# LSM6DSV_MAG_JST125.net
KiCad netlist of a schematic drawn in EasyEDA Pro
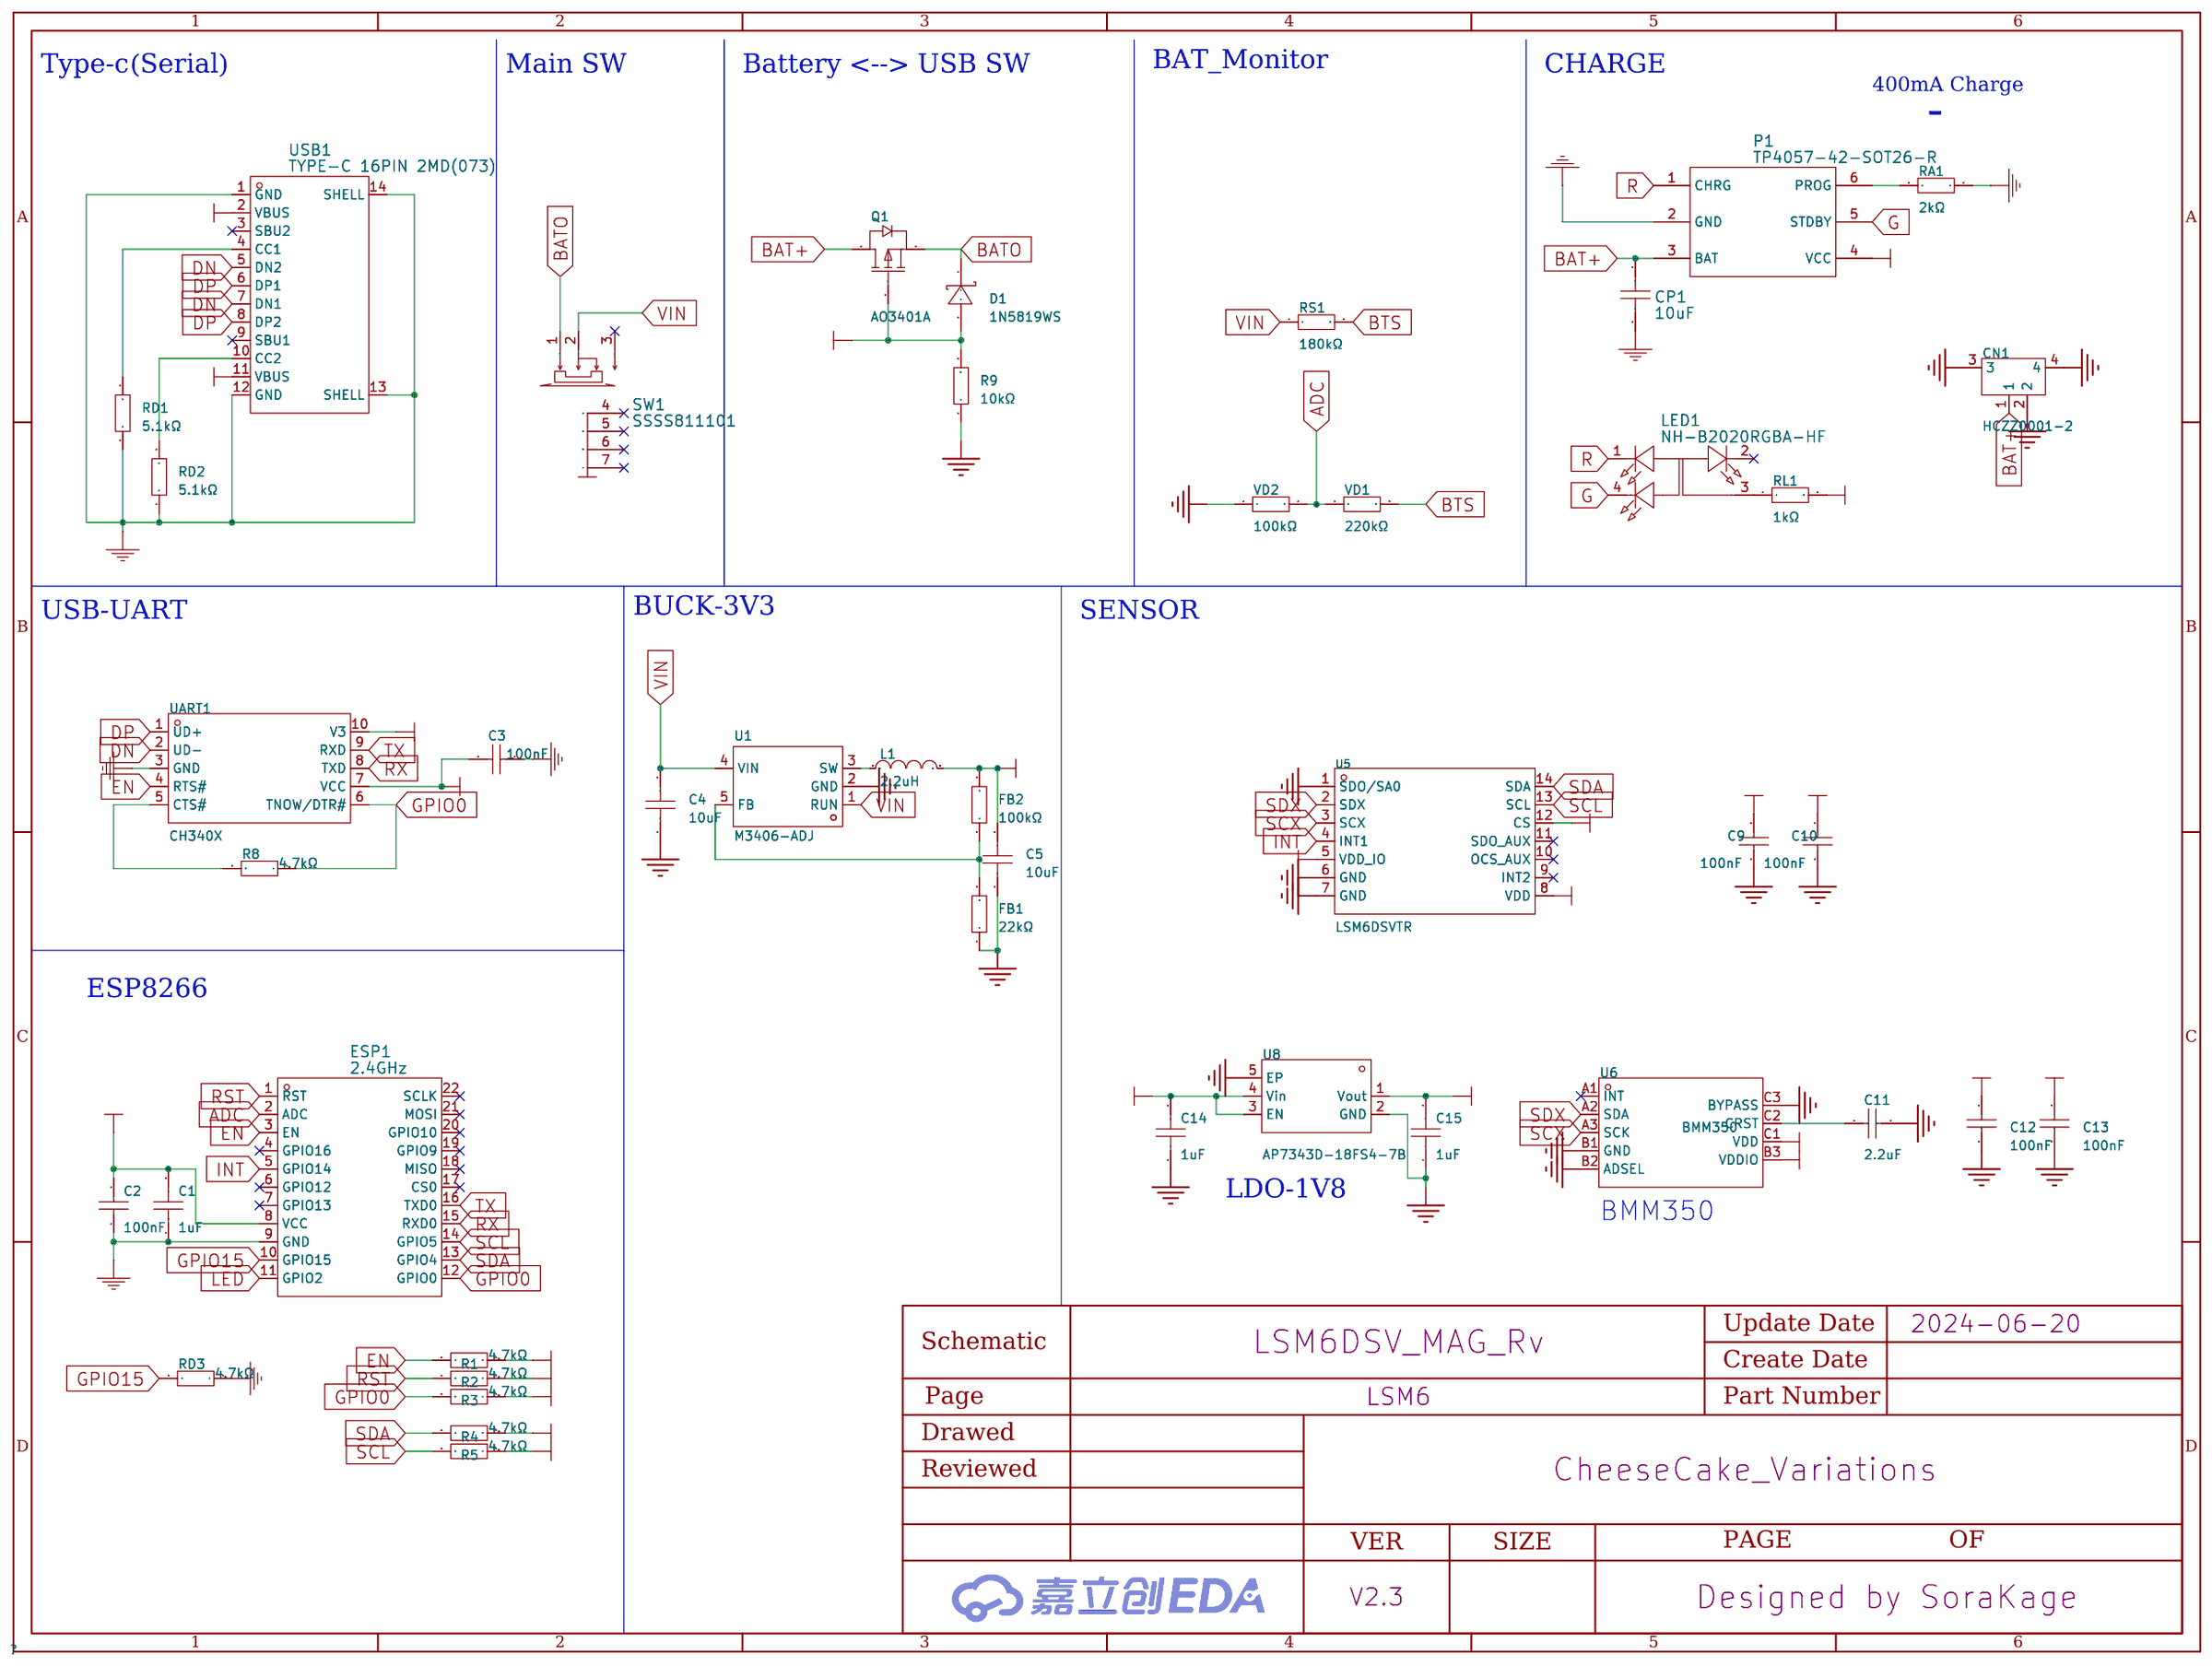
[diagram p0: schematic sheet]

(export (version "E")
  (design (tool "Eeschema 10.0.6"))
  (components
    (comp (ref "C1")
      (value "1uF")
      (footprint "easyedapro:C0402")
      (description "容值:1uF;精度:±10%;额定电压:25V;材质(温度系数):X5R;")
      (fields
        (field (name "Manufacturer Part") "CL05A105KA5NQNC")
        (field (name "Manufacturer") "SAMSUNG(三星)")
      )
      (libsource (lib "easyedapro") (part "CL05A105KA5NQNC"))
    )
    (comp (ref "C2")
      (value "100nF")
      (footprint "easyedapro:C0402")
      (description "容值:100nF;精度:±10%;额定电压:16V;材质(温度系数):X7R;")
      (fields
        (field (name "Manufacturer Part") "CL05B104KO5NNNC")
        (field (name "Manufacturer") "SAMSUNG(三星)")
      )
      (libsource (lib "easyedapro") (part "CL05B104KO5NNNC"))
    )
    (comp (ref "C3")
      (value "100nF")
      (footprint "easyedapro:C0402")
      (description "容值:100nF;精度:±10%;额定电压:16V;材质(温度系数):X7R;")
      (fields
        (field (name "Manufacturer Part") "CL05B104KO5NNNC")
        (field (name "Manufacturer") "SAMSUNG(三星)")
      )
      (libsource (lib "easyedapro") (part "CL05B104KO5NNNC"))
    )
    (comp (ref "C4")
      (value "10uF")
      (footprint "easyedapro:C0603")
      (description "容值:10uF;精度:±10%;额定电压:10V;材质(温度系数):X5R;")
      (fields
        (field (name "Manufacturer Part") "CL10A106KP8NNNC")
        (field (name "Manufacturer") "SAMSUNG(三星)")
      )
      (libsource (lib "easyedapro") (part "CL10A106KP8NNNC"))
    )
    (comp (ref "C5")
      (value "10uF")
      (footprint "easyedapro:C0603")
      (description "容值:10uF;精度:±10%;额定电压:10V;材质(温度系数):X5R;")
      (fields
        (field (name "Manufacturer Part") "CL10A106KP8NNNC")
        (field (name "Manufacturer") "SAMSUNG(三星)")
      )
      (libsource (lib "easyedapro") (part "CL10A106KP8NNNC"))
    )
    (comp (ref "C9")
      (value "100nF")
      (footprint "easyedapro:C0402")
      (description "容值:100nF;精度:±10%;额定电压:16V;材质(温度系数):X7R;")
      (fields
        (field (name "Manufacturer Part") "CL05B104KO5NNNC")
        (field (name "Manufacturer") "SAMSUNG(三星)")
      )
      (libsource (lib "easyedapro") (part "CL05B104KO5NNNC"))
    )
    (comp (ref "C10")
      (value "100nF")
      (footprint "easyedapro:C0402")
      (description "容值:100nF;精度:±10%;额定电压:16V;材质(温度系数):X7R;")
      (fields
        (field (name "Manufacturer Part") "CL05B104KO5NNNC")
        (field (name "Manufacturer") "SAMSUNG(三星)")
      )
      (libsource (lib "easyedapro") (part "CL05B104KO5NNNC"))
    )
    (comp (ref "C11")
      (value "2.2uF")
      (footprint "easyedapro:C0805")
      (description "容值:2.2uF;精度:±10%;额定电压:10V;材质(温度系数):X7R;")
      (fields
        (field (name "Manufacturer Part") "GCM21BR71A225KA37L")
        (field (name "Manufacturer") "muRata(村田)")
      )
      (libsource (lib "easyedapro") (part "GCM21BR71A225KA37L"))
    )
    (comp (ref "C12")
      (value "100nF")
      (footprint "easyedapro:C0402")
      (description "容值:100nF;精度:±10%;额定电压:16V;材质(温度系数):X7R;")
      (fields
        (field (name "Manufacturer Part") "CL05B104KO5NNNC")
        (field (name "Manufacturer") "SAMSUNG(三星)")
      )
      (libsource (lib "easyedapro") (part "CL05B104KO5NNNC"))
    )
    (comp (ref "C13")
      (value "100nF")
      (footprint "easyedapro:C0402")
      (description "容值:100nF;精度:±10%;额定电压:16V;材质(温度系数):X7R;")
      (fields
        (field (name "Manufacturer Part") "CL05B104KO5NNNC")
        (field (name "Manufacturer") "SAMSUNG(三星)")
      )
      (libsource (lib "easyedapro") (part "CL05B104KO5NNNC"))
    )
    (comp (ref "C14")
      (value "1uF")
      (footprint "easyedapro:C0402")
      (description "容值:1uF;精度:±10%;额定电压:25V;材质(温度系数):X5R;")
      (fields
        (field (name "Manufacturer Part") "CL05A105KA5NQNC")
        (field (name "Manufacturer") "SAMSUNG(三星)")
      )
      (libsource (lib "easyedapro") (part "CL05A105KA5NQNC"))
    )
    (comp (ref "C15")
      (value "1uF")
      (footprint "easyedapro:C0402")
      (description "容值:1uF;精度:±10%;额定电压:25V;材质(温度系数):X5R;")
      (fields
        (field (name "Manufacturer Part") "CL05A105KA5NQNC")
        (field (name "Manufacturer") "SAMSUNG(三星)")
      )
      (libsource (lib "easyedapro") (part "CL05A105KA5NQNC"))
    )
    (comp (ref "CN1")
      (value "HCZZ0001-2")
      (footprint "easyedapro:CONN-SMD_2P-P1.25_HC_HCZZ0001-2")
      (fields (field (name "Manufacturer") "HC(虹成电子)"))
      (libsource (lib "easyedapro") (part "HCZZ0001-2"))
    )
    (comp (ref "CP1")
      (value "10uF")
      (footprint "easyedapro:C0603")
      (fields
        (field (name "Manufacturer Part") "CL10A106KP8NNNC")
        (field (name "Manufacturer") "SAMSUNG(三星)")
      )
      (libsource (lib "easyedapro") (part "10uF"))
    )
    (comp (ref "D1")
      (value "1N5819WS")
      (footprint "easyedapro:SOD-323_L1.8-W1.3-LS2.5-RD")
      (description "直流反向耐压(Vr):40V;平均整流电流(Io):1A;正向压降(Vf):600mV@1A;")
      (fields (field (name "Manufacturer") "Hottech(合科泰)"))
      (libsource (lib "easyedapro") (part "1N5819WS"))
    )
    (comp (ref "ESP1")
      (value "2.4GHz")
      (description "核心处理器:ESP8266芯片;频率:2.4GHz;天线形式:板载PCB天线;发射功率:16dBm;接收灵敏度:-90dBm;")
      (fields
        (field (name "Manufacturer Part") "ESP-12F(ESP8266MOD)")
        (field (name "Manufacturer") "Ai-Thinker(安信可)")
      )
      (libsource (lib "easyedapro") (part "ESP-12F(ESP8266MOD)"))
    )
    (comp (ref "FB1")
      (value "22kΩ")
      (footprint "easyedapro:R0402")
      (description "电阻类型:厚膜电阻;阻值:22kΩ;精度:±1%;功率:62.5mW;")
      (fields
        (field (name "Manufacturer Part") "0402WGF2202TCE")
        (field (name "Manufacturer") "UNI-ROYAL(厚声)")
      )
      (libsource (lib "easyedapro") (part "0402WGF2202TCE"))
    )
    (comp (ref "FB2")
      (value "100kΩ")
      (footprint "easyedapro:R0402")
      (description "电阻类型:厚膜电阻;阻值:100kΩ;精度:±1%;功率:62.5mW;")
      (fields
        (field (name "Manufacturer Part") "0402WGF1003TCE")
        (field (name "Manufacturer") "UNI-ROYAL(厚声)")
      )
      (libsource (lib "easyedapro") (part "0402WGF1003TCE"))
    )
    (comp (ref "L1")
      (value "2.2uH")
      (footprint "easyedapro:IND-SMD_L2.5-W2.0_YXMBL252010P")
      (description "类型:一体成型电感;电感值:2.2uH;精度:±20%;额定电流:2.1A;饱和电流(Isat):3A;")
      (fields (field (name "Manufacturer Part") "APH252010T2R2M") (field (name "Manufacturer") "APV(爱普微)"))
      (libsource (lib "easyedapro") (part "APH252010T2R2M"))
    )
    (comp (ref "LED1")
      (value "NH-B2020RGBA-HF")
      (footprint "easyedapro:LED-ARRAY-SMD_4P-L2.1-W2.1-TL_NH-B2020RGBA")
      (fields (field (name "Manufacturer") "国星光电"))
      (libsource (lib "easyedapro") (part "NH-B2020RGBA-HF"))
    )
    (comp (ref "P1")
      (value "TP4057-42-SOT26-R")
      (footprint "easyedapro:SOT-23-6_L2.9-W1.6-P0.95-LS2.8-BL")
      (fields (field (name "Manufacturer") "TOPPOWER(南京拓微)"))
      (libsource (lib "easyedapro") (part "TP4057"))
    )
    (comp (ref "Q1")
      (value "AO3401A")
      (footprint "easyedapro:SOT-23_L2.9-W1.3-P1.90-LS2.4-BR")
      (description "类型:P沟道;漏源电压(Vdss):30V;连续漏极电流(Id):4A;功率(Pd):1.4W;导通电阻(RDS(on)@Vgs,Id):44mΩ@10V,4.3A;")
      (fields (field (name "Manufacturer") "AOS"))
      (libsource (lib "easyedapro") (part "AO3401A"))
    )
    (comp (ref "R1")
      (value "4.7kΩ")
      (footprint "easyedapro:R0402")
      (description "电阻类型:厚膜电阻;阻值:4.7kΩ;精度:±1%;功率:62.5mW;")
      (fields
        (field (name "Manufacturer Part") "0402WGF4701TCE")
        (field (name "Manufacturer") "UNI-ROYAL(厚声)")
      )
      (libsource (lib "easyedapro") (part "0402WGF4701TCE"))
    )
    (comp (ref "R2")
      (value "4.7kΩ")
      (footprint "easyedapro:R0402")
      (description "电阻类型:厚膜电阻;阻值:4.7kΩ;精度:±1%;功率:62.5mW;")
      (fields
        (field (name "Manufacturer Part") "0402WGF4701TCE")
        (field (name "Manufacturer") "UNI-ROYAL(厚声)")
      )
      (libsource (lib "easyedapro") (part "0402WGF4701TCE"))
    )
    (comp (ref "R3")
      (value "4.7kΩ")
      (footprint "easyedapro:R0402")
      (description "电阻类型:厚膜电阻;阻值:4.7kΩ;精度:±1%;功率:62.5mW;")
      (fields
        (field (name "Manufacturer Part") "0402WGF4701TCE")
        (field (name "Manufacturer") "UNI-ROYAL(厚声)")
      )
      (libsource (lib "easyedapro") (part "0402WGF4701TCE"))
    )
    (comp (ref "R4")
      (value "4.7kΩ")
      (footprint "easyedapro:R0402")
      (description "电阻类型:厚膜电阻;阻值:4.7kΩ;精度:±1%;功率:62.5mW;")
      (fields
        (field (name "Manufacturer Part") "0402WGF4701TCE")
        (field (name "Manufacturer") "UNI-ROYAL(厚声)")
      )
      (libsource (lib "easyedapro") (part "0402WGF4701TCE"))
    )
    (comp (ref "R5")
      (value "4.7kΩ")
      (footprint "easyedapro:R0402")
      (description "电阻类型:厚膜电阻;阻值:4.7kΩ;精度:±1%;功率:62.5mW;")
      (fields
        (field (name "Manufacturer Part") "0402WGF4701TCE")
        (field (name "Manufacturer") "UNI-ROYAL(厚声)")
      )
      (libsource (lib "easyedapro") (part "0402WGF4701TCE"))
    )
    (comp (ref "R8")
      (value "4.7kΩ")
      (footprint "easyedapro:R0402")
      (description "电阻类型:厚膜电阻;阻值:4.7kΩ;精度:±1%;功率:62.5mW;")
      (fields
        (field (name "Manufacturer Part") "0402WGF4701TCE")
        (field (name "Manufacturer") "UNI-ROYAL(厚声)")
      )
      (libsource (lib "easyedapro") (part "0402WGF4701TCE"))
    )
    (comp (ref "R9")
      (value "10kΩ")
      (footprint "easyedapro:R0402")
      (description "电阻类型:厚膜电阻;阻值:10kΩ;精度:±1%;功率:62.5mW;")
      (fields
        (field (name "Manufacturer Part") "0402WGF1002TCE")
        (field (name "Manufacturer") "UNI-ROYAL(厚声)")
      )
      (libsource (lib "easyedapro") (part "0402WGF1002TCE"))
    )
    (comp (ref "RA1")
      (value "2kΩ")
      (footprint "easyedapro:R0402")
      (description "电阻类型:厚膜电阻;阻值:2kΩ;精度:±1%;功率:62.5mW;")
      (fields
        (field (name "Manufacturer Part") "0402WGF2001TCE")
        (field (name "Manufacturer") "UNI-ROYAL(厚声)")
      )
      (libsource (lib "easyedapro") (part "0402WGF2001TCE"))
    )
    (comp (ref "RD1")
      (value "5.1kΩ")
      (footprint "easyedapro:R0402")
      (description "电阻类型:厚膜电阻;阻值:5.1kΩ;精度:±1%;功率:62.5mW;")
      (fields
        (field (name "Manufacturer Part") "0402WGF5101TCE")
        (field (name "Manufacturer") "UNI-ROYAL(厚声)")
      )
      (libsource (lib "easyedapro") (part "0402WGF5101TCE"))
    )
    (comp (ref "RD2")
      (value "5.1kΩ")
      (footprint "easyedapro:R0402")
      (description "电阻类型:厚膜电阻;阻值:5.1kΩ;精度:±1%;功率:62.5mW;")
      (fields
        (field (name "Manufacturer Part") "0402WGF5101TCE")
        (field (name "Manufacturer") "UNI-ROYAL(厚声)")
      )
      (libsource (lib "easyedapro") (part "0402WGF5101TCE"))
    )
    (comp (ref "RD3")
      (value "4.7kΩ")
      (footprint "easyedapro:R0402")
      (description "电阻类型:厚膜电阻;阻值:4.7kΩ;精度:±1%;功率:62.5mW;")
      (fields
        (field (name "Manufacturer Part") "0402WGF4701TCE")
        (field (name "Manufacturer") "UNI-ROYAL(厚声)")
      )
      (libsource (lib "easyedapro") (part "0402WGF4701TCE"))
    )
    (comp (ref "RL1")
      (value "1kΩ")
      (footprint "easyedapro:R0402")
      (description "电阻类型:厚膜电阻;阻值:1kΩ;精度:±1%;功率:62.5mW;")
      (fields
        (field (name "Manufacturer Part") "0402WGF1001TCE")
        (field (name "Manufacturer") "UNI-ROYAL(厚声)")
      )
      (libsource (lib "easyedapro") (part "0402WGF1001TCE"))
    )
    (comp (ref "RS1")
      (value "180kΩ")
      (footprint "easyedapro:R0402")
      (description "阻值:180kΩ;精度:±1%;功率:62.5mW;温度系数:±100ppm/°C;电阻类型:厚膜电阻;")
      (fields
        (field (name "Manufacturer Part") "0402WGF1803TCE")
        (field (name "Manufacturer") "UNI-ROYAL(厚声)")
      )
      (libsource (lib "easyedapro") (part "0402WGF1803TCE"))
    )
    (comp (ref "SW1")
      (value "SSSS811101")
      (footprint "easyedapro:SW-SMD_SSSS811101")
      (fields (field (name "Manufacturer") "ALPSALPINE(阿尔卑斯阿尔派)"))
      (libsource (lib "easyedapro") (part "SSSS811101"))
    )
    (comp (ref "U1")
      (value "M3406-ADJ")
      (footprint "easyedapro:SOT-23-5_L3.0-W1.7-P0.95-LS2.8-BR")
      (description "功能类型:降压型;同步整流:-;输出通道数:-;拓扑结构:-;输入电压:-;输出电流(最大值):-;开关频率:-;")
      (fields (field (name "Manufacturer") "西安航天民芯"))
      (libsource (lib "easyedapro") (part "M3406"))
    )
    (comp (ref "U5")
      (value "LSM6DSVTR")
      (footprint "easyedapro:LGA-14_L3.0-W2.5-P0.50-TL")
      (description "传感器类型:加速度计陀螺仪;")
      (fields (field (name "Manufacturer") "ST(意法半导体)"))
      (libsource (lib "easyedapro") (part "LSM6DSVTR"))
    )
    (comp (ref "U6")
      (value "BMM350")
      (footprint "easyedapro:WLCSP-9_L1.3-W1.3-R3-C3-P0.40-TL")
      (libsource (lib "easyedapro") (part "BMM350"))
    )
    (comp (ref "U8")
      (value "AP7343D-18FS4-7B")
      (footprint "easyedapro:X2-DFN1010-4_L1.0-W1.0-P0.65-BL-EP")
      (description "输出类型:固定;最大输入电压:5.25V;输出电压:1.8V;最大输出电流:300mA;电源纹波抑制比(PSRR):75dB@(1kHz);输出极性:正极;")
      (fields (field (name "Manufacturer") "DIODES(美台)"))
      (libsource (lib "easyedapro") (part "AP7343D-18FS4-7B"))
    )
    (comp (ref "UART1")
      (value "CH340X")
      (footprint "easyedapro:MSOP-10_L3.0-W3.0-P0.50-LS5.0-BL")
      (fields (field (name "Manufacturer") "WCH(南京沁恒)"))
      (libsource (lib "easyedapro") (part "CH340X"))
    )
    (comp (ref "USB1")
      (value "TYPE-C 16PIN 2MD(073)")
      (footprint "easyedapro:USB-C-SMD_TYPE-C-6PIN-2MD-073")
      (fields (field (name "Manufacturer") "SHOU HAN(首韩)"))
      (libsource (lib "easyedapro") (part "TYPE-C 16PIN 2MD(073)"))
    )
    (comp (ref "VD1")
      (value "220kΩ")
      (footprint "easyedapro:R0402")
      (description "电阻类型:厚膜电阻;阻值:220kΩ;精度:±1%;功率:62.5mW;")
      (fields
        (field (name "Manufacturer Part") "0402WGF2203TCE")
        (field (name "Manufacturer") "UNI-ROYAL(厚声)")
      )
      (libsource (lib "easyedapro") (part "0402WGF2203TCE"))
    )
    (comp (ref "VD2")
      (value "100kΩ")
      (footprint "easyedapro:R0402")
      (description "电阻类型:厚膜电阻;阻值:100kΩ;精度:±1%;功率:62.5mW;")
      (fields
        (field (name "Manufacturer Part") "0402WGF1003TCE")
        (field (name "Manufacturer") "UNI-ROYAL(厚声)")
      )
      (libsource (lib "easyedapro") (part "0402WGF1003TCE"))
    )
  )
  (nets
    (net (code "1") (name "+5V") (class "Default")
      (node (ref "D1") (pin "2") (pinfunction "A_2") (pintype "unspecified"))
      (node (ref "P1") (pin "4") (pinfunction "VCC_4") (pintype "unspecified"))
      (node (ref "Q1") (pin "1") (pinfunction "G_1") (pintype "input"))
      (node (ref "R9") (pin "2") (pinfunction "2_2") (pintype "input"))
      (node (ref "RL1") (pin "2") (pinfunction "2_2") (pintype "input"))
      (node (ref "USB1") (pin "11") (pinfunction "VBUS_11") (pintype "input"))
      (node (ref "USB1") (pin "2") (pinfunction "VBUS_2") (pintype "input"))
    )
    (net (code "2") (name "1V8") (class "Default")
      (node (ref "C12") (pin "2") (pinfunction "2_2") (pintype "input"))
      (node (ref "C15") (pin "2") (pinfunction "2_2") (pintype "unspecified"))
      (node (ref "U6") (pin "C1") (pinfunction "VDD_C1") (pintype "unspecified"))
      (node (ref "U8") (pin "1") (pinfunction "Vout_1") (pintype "input"))
    )
    (net (code "3") (name "3V3") (class "Default")
      (node (ref "C1") (pin "2") (pinfunction "2_2") (pintype "unspecified"))
      (node (ref "C10") (pin "1") (pinfunction "1_1") (pintype "input"))
      (node (ref "C13") (pin "2") (pinfunction "2_2") (pintype "input"))
      (node (ref "C14") (pin "2") (pinfunction "2_2") (pintype "unspecified"))
      (node (ref "C2") (pin "2") (pinfunction "2_2") (pintype "input"))
      (node (ref "C3") (pin "2") (pinfunction "2_2") (pintype "input"))
      (node (ref "C5") (pin "2") (pinfunction "2_2") (pintype "unspecified"))
      (node (ref "C9") (pin "1") (pinfunction "1_1") (pintype "input"))
      (node (ref "ESP1") (pin "8") (pinfunction "VCC_8") (pintype "input"))
      (node (ref "FB2") (pin "2") (pinfunction "2_2") (pintype "input"))
      (node (ref "L1") (pin "2") (pinfunction "2_2") (pintype "unspecified"))
      (node (ref "R1") (pin "1") (pinfunction "1_1") (pintype "input"))
      (node (ref "R2") (pin "1") (pinfunction "1_1") (pintype "input"))
      (node (ref "R3") (pin "1") (pinfunction "1_1") (pintype "input"))
      (node (ref "R4") (pin "1") (pinfunction "1_1") (pintype "input"))
      (node (ref "R5") (pin "1") (pinfunction "1_1") (pintype "input"))
      (node (ref "U5") (pin "12") (pinfunction "CS_12") (pintype "input"))
      (node (ref "U5") (pin "5") (pinfunction "VDD_IO_5") (pintype "input"))
      (node (ref "U5") (pin "8") (pinfunction "VDD_8") (pintype "input"))
      (node (ref "U6") (pin "B3") (pinfunction "VDDIO_B3") (pintype "unspecified"))
      (node (ref "U8") (pin "3") (pinfunction "EN_3") (pintype "input"))
      (node (ref "U8") (pin "4") (pinfunction "Vin_4") (pintype "input"))
      (node (ref "UART1") (pin "10") (pinfunction "V3_10") (pintype "unspecified"))
      (node (ref "UART1") (pin "7") (pinfunction "VCC_7") (pintype "unspecified"))
    )
    (net (code "4") (name "ADC") (class "Default")
      (node (ref "ESP1") (pin "2") (pinfunction "ADC_2") (pintype "input"))
      (node (ref "VD1") (pin "1") (pinfunction "1_1") (pintype "input"))
      (node (ref "VD2") (pin "2") (pinfunction "2_2") (pintype "input"))
    )
    (net (code "5") (name "BAT+") (class "Default")
      (node (ref "CN1") (pin "1") (pinfunction "1_1") (pintype "unspecified"))
      (node (ref "CP1") (pin "2") (pinfunction "2_2") (pintype "input"))
      (node (ref "P1") (pin "3") (pinfunction "BAT_3") (pintype "unspecified"))
      (node (ref "Q1") (pin "3") (pinfunction "D_3") (pintype "input"))
    )
    (net (code "6") (name "BATO") (class "Default")
      (node (ref "D1") (pin "1") (pinfunction "K_1") (pintype "unspecified"))
      (node (ref "Q1") (pin "2") (pinfunction "S_2") (pintype "input"))
      (node (ref "SW1") (pin "1") (pinfunction "1_1") (pintype "input"))
    )
    (net (code "7") (name "BTS") (class "Default")
      (node (ref "RS1") (pin "2") (pinfunction "2_2") (pintype "input"))
      (node (ref "VD1") (pin "2") (pinfunction "2_2") (pintype "input"))
    )
    (net (code "8") (name "DN") (class "Default")
      (node (ref "UART1") (pin "2") (pinfunction "UD-_2") (pintype "unspecified"))
      (node (ref "USB1") (pin "5") (pinfunction "DN2_5") (pintype "input"))
      (node (ref "USB1") (pin "7") (pinfunction "DN1_7") (pintype "input"))
    )
    (net (code "9") (name "DP") (class "Default")
      (node (ref "UART1") (pin "1") (pinfunction "UD+_1") (pintype "unspecified"))
      (node (ref "USB1") (pin "6") (pinfunction "DP1_6") (pintype "input"))
      (node (ref "USB1") (pin "8") (pinfunction "DP2_8") (pintype "input"))
    )
    (net (code "10") (name "EN") (class "Default")
      (node (ref "ESP1") (pin "3") (pinfunction "EN_3") (pintype "input"))
      (node (ref "R1") (pin "2") (pinfunction "2_2") (pintype "input"))
      (node (ref "UART1") (pin "4") (pinfunction "RTS#_4") (pintype "unspecified"))
    )
    (net (code "11") (name "G") (class "Default")
      (node (ref "LED1") (pin "4") (pinfunction "-_4") (pintype "input"))
      (node (ref "P1") (pin "5") (pinfunction "STDBY_5") (pintype "unspecified"))
    )
    (net (code "12") (name "GND") (class "Default")
      (node (ref "C1") (pin "1") (pinfunction "1_1") (pintype "unspecified"))
      (node (ref "C10") (pin "2") (pinfunction "2_2") (pintype "input"))
      (node (ref "C11") (pin "2") (pinfunction "2_2") (pintype "input"))
      (node (ref "C12") (pin "1") (pinfunction "1_1") (pintype "input"))
      (node (ref "C13") (pin "1") (pinfunction "1_1") (pintype "input"))
      (node (ref "C14") (pin "1") (pinfunction "1_1") (pintype "unspecified"))
      (node (ref "C15") (pin "1") (pinfunction "1_1") (pintype "unspecified"))
      (node (ref "C2") (pin "1") (pinfunction "1_1") (pintype "input"))
      (node (ref "C3") (pin "1") (pinfunction "1_1") (pintype "input"))
      (node (ref "C4") (pin "1") (pinfunction "1_1") (pintype "unspecified"))
      (node (ref "C5") (pin "1") (pinfunction "1_1") (pintype "unspecified"))
      (node (ref "C9") (pin "2") (pinfunction "2_2") (pintype "input"))
      (node (ref "CN1") (pin "2") (pinfunction "2_2") (pintype "unspecified"))
      (node (ref "CN1") (pin "3") (pinfunction "3_3") (pintype "unspecified"))
      (node (ref "CN1") (pin "4") (pinfunction "4_4") (pintype "unspecified"))
      (node (ref "CP1") (pin "1") (pinfunction "1_1") (pintype "input"))
      (node (ref "ESP1") (pin "9") (pinfunction "GND_9") (pintype "input"))
      (node (ref "FB1") (pin "1") (pinfunction "1_1") (pintype "input"))
      (node (ref "P1") (pin "2") (pinfunction "GND_2") (pintype "unspecified"))
      (node (ref "R9") (pin "1") (pinfunction "1_1") (pintype "input"))
      (node (ref "RA1") (pin "2") (pinfunction "2_2") (pintype "input"))
      (node (ref "RD1") (pin "1") (pinfunction "1_1") (pintype "input"))
      (node (ref "RD2") (pin "1") (pinfunction "1_1") (pintype "input"))
      (node (ref "RD3") (pin "1") (pinfunction "1_1") (pintype "input"))
      (node (ref "U1") (pin "2") (pinfunction "GND_2") (pintype "input"))
      (node (ref "U5") (pin "1") (pinfunction "SDO/SA0_1") (pintype "input"))
      (node (ref "U5") (pin "6") (pinfunction "GND_6") (pintype "input"))
      (node (ref "U5") (pin "7") (pinfunction "GND_7") (pintype "input"))
      (node (ref "U6") (pin "B1") (pinfunction "GND_B1") (pintype "unspecified"))
      (node (ref "U6") (pin "B2") (pinfunction "ADSEL_B2") (pintype "unspecified"))
      (node (ref "U6") (pin "C3") (pinfunction "BYPASS_C3") (pintype "unspecified"))
      (node (ref "U8") (pin "2") (pinfunction "GND_2") (pintype "input"))
      (node (ref "U8") (pin "5") (pinfunction "EP_5") (pintype "input"))
      (node (ref "UART1") (pin "3") (pinfunction "GND_3") (pintype "unspecified"))
      (node (ref "USB1") (pin "1") (pinfunction "GND_1") (pintype "input"))
      (node (ref "USB1") (pin "12") (pinfunction "GND_12") (pintype "input"))
      (node (ref "USB1") (pin "13") (pinfunction "SHELL_13") (pintype "input"))
      (node (ref "USB1") (pin "14") (pinfunction "SHELL_14") (pintype "input"))
      (node (ref "VD2") (pin "1") (pinfunction "1_1") (pintype "input"))
    )
    (net (code "13") (name "GPIO0") (class "Default")
      (node (ref "ESP1") (pin "12") (pinfunction "GPIO0_12") (pintype "input"))
      (node (ref "R3") (pin "2") (pinfunction "2_2") (pintype "input"))
      (node (ref "R8") (pin "1") (pinfunction "1_1") (pintype "input"))
      (node (ref "UART1") (pin "6") (pinfunction "TNOW/DTR#_6") (pintype "unspecified"))
    )
    (net (code "14") (name "GPIO15") (class "Default")
      (node (ref "ESP1") (pin "10") (pinfunction "GPIO15_10") (pintype "input"))
      (node (ref "RD3") (pin "2") (pinfunction "2_2") (pintype "input"))
    )
    (net (code "15") (name "INT") (class "Default")
      (node (ref "ESP1") (pin "5") (pinfunction "GPIO14_5") (pintype "input"))
      (node (ref "U5") (pin "4") (pinfunction "INT1_4") (pintype "input"))
    )
    (net (code "16") (name "LED") (class "Default")
      (node (ref "ESP1") (pin "11") (pinfunction "GPIO2_11") (pintype "input"))
    )
    (net (code "17") (name "Net-(LED1-+)") (class "Default")
      (node (ref "LED1") (pin "3") (pinfunction "+_3") (pintype "input"))
      (node (ref "RL1") (pin "1") (pinfunction "1_1") (pintype "input"))
    )
    (net (code "18") (name "Net-(P1-PROG)") (class "Default")
      (node (ref "P1") (pin "6") (pinfunction "PROG_6") (pintype "unspecified"))
      (node (ref "RA1") (pin "1") (pinfunction "1_1") (pintype "input"))
    )
    (net (code "19") (name "Net-(U1-FB)") (class "Default")
      (node (ref "FB1") (pin "2") (pinfunction "2_2") (pintype "input"))
      (node (ref "FB2") (pin "1") (pinfunction "1_1") (pintype "input"))
      (node (ref "U1") (pin "5") (pinfunction "FB_5") (pintype "input"))
    )
    (net (code "20") (name "Net-(U1-SW)") (class "Default")
      (node (ref "L1") (pin "1") (pinfunction "1_1") (pintype "unspecified"))
      (node (ref "U1") (pin "3") (pinfunction "SW_3") (pintype "input"))
    )
    (net (code "21") (name "Net-(U6-CRST)") (class "Default")
      (node (ref "C11") (pin "1") (pinfunction "1_1") (pintype "input"))
      (node (ref "U6") (pin "C2") (pinfunction "CRST_C2") (pintype "unspecified"))
    )
    (net (code "22") (name "Net-(UART1-CTS#)") (class "Default")
      (node (ref "R8") (pin "2") (pinfunction "2_2") (pintype "input"))
      (node (ref "UART1") (pin "5") (pinfunction "CTS#_5") (pintype "unspecified"))
    )
    (net (code "23") (name "Net-(USB1-CC1)") (class "Default")
      (node (ref "RD1") (pin "2") (pinfunction "2_2") (pintype "input"))
      (node (ref "USB1") (pin "4") (pinfunction "CC1_4") (pintype "input"))
    )
    (net (code "24") (name "Net-(USB1-CC2)") (class "Default")
      (node (ref "RD2") (pin "2") (pinfunction "2_2") (pintype "input"))
      (node (ref "USB1") (pin "10") (pinfunction "CC2_10") (pintype "input"))
    )
    (net (code "25") (name "R") (class "Default")
      (node (ref "LED1") (pin "1") (pinfunction "-_1") (pintype "input"))
      (node (ref "P1") (pin "1") (pinfunction "CHRG_1") (pintype "unspecified"))
    )
    (net (code "26") (name "RST") (class "Default")
      (node (ref "ESP1") (pin "1") (pinfunction "RST_1") (pintype "input"))
      (node (ref "R2") (pin "2") (pinfunction "2_2") (pintype "input"))
    )
    (net (code "27") (name "RX") (class "Default")
      (node (ref "ESP1") (pin "15") (pinfunction "RXD0_15") (pintype "input"))
      (node (ref "UART1") (pin "8") (pinfunction "TXD_8") (pintype "unspecified"))
    )
    (net (code "28") (name "SCL") (class "Default")
      (node (ref "ESP1") (pin "14") (pinfunction "GPIO5_14") (pintype "input"))
      (node (ref "R5") (pin "2") (pinfunction "2_2") (pintype "input"))
      (node (ref "U5") (pin "13") (pinfunction "SCL_13") (pintype "input"))
    )
    (net (code "29") (name "SCX") (class "Default")
      (node (ref "U5") (pin "3") (pinfunction "SCX_3") (pintype "input"))
      (node (ref "U6") (pin "A3") (pinfunction "SCK_A3") (pintype "unspecified"))
    )
    (net (code "30") (name "SDA") (class "Default")
      (node (ref "ESP1") (pin "13") (pinfunction "GPIO4_13") (pintype "input"))
      (node (ref "R4") (pin "2") (pinfunction "2_2") (pintype "input"))
      (node (ref "U5") (pin "14") (pinfunction "SDA_14") (pintype "input"))
    )
    (net (code "31") (name "SDX") (class "Default")
      (node (ref "U5") (pin "2") (pinfunction "SDX_2") (pintype "input"))
      (node (ref "U6") (pin "A2") (pinfunction "SDA_A2") (pintype "unspecified"))
    )
    (net (code "32") (name "TX") (class "Default")
      (node (ref "ESP1") (pin "16") (pinfunction "TXD0_16") (pintype "input"))
      (node (ref "UART1") (pin "9") (pinfunction "RXD_9") (pintype "unspecified"))
    )
    (net (code "33") (name "VIN") (class "Default")
      (node (ref "C4") (pin "2") (pinfunction "2_2") (pintype "unspecified"))
      (node (ref "RS1") (pin "1") (pinfunction "1_1") (pintype "input"))
      (node (ref "SW1") (pin "2") (pinfunction "2_2") (pintype "input"))
      (node (ref "U1") (pin "1") (pinfunction "RUN_1") (pintype "input"))
      (node (ref "U1") (pin "4") (pinfunction "VIN_4") (pintype "input"))
    )
    (net (code "34") (name "unconnected-(ESP1-CS0-Pad17)") (class "Default")
      (node (ref "ESP1") (pin "17") (pinfunction "CS0_17") (pintype "input+no_connect"))
    )
    (net (code "35") (name "unconnected-(ESP1-GPIO9-Pad19)") (class "Default")
      (node (ref "ESP1") (pin "19") (pinfunction "GPIO9_19") (pintype "input+no_connect"))
    )
    (net (code "36") (name "unconnected-(ESP1-GPIO10-Pad20)") (class "Default")
      (node (ref "ESP1") (pin "20") (pinfunction "GPIO10_20") (pintype "input+no_connect"))
    )
    (net (code "37") (name "unconnected-(ESP1-GPIO12-Pad6)") (class "Default")
      (node (ref "ESP1") (pin "6") (pinfunction "GPIO12_6") (pintype "input+no_connect"))
    )
    (net (code "38") (name "unconnected-(ESP1-GPIO13-Pad7)") (class "Default")
      (node (ref "ESP1") (pin "7") (pinfunction "GPIO13_7") (pintype "input+no_connect"))
    )
    (net (code "39") (name "unconnected-(ESP1-GPIO16-Pad4)") (class "Default")
      (node (ref "ESP1") (pin "4") (pinfunction "GPIO16_4") (pintype "input+no_connect"))
    )
    (net (code "40") (name "unconnected-(ESP1-MISO-Pad18)") (class "Default")
      (node (ref "ESP1") (pin "18") (pinfunction "MISO_18") (pintype "input+no_connect"))
    )
    (net (code "41") (name "unconnected-(ESP1-MOSI-Pad21)") (class "Default")
      (node (ref "ESP1") (pin "21") (pinfunction "MOSI_21") (pintype "input+no_connect"))
    )
    (net (code "42") (name "unconnected-(ESP1-SCLK-Pad22)") (class "Default")
      (node (ref "ESP1") (pin "22") (pinfunction "SCLK_22") (pintype "input+no_connect"))
    )
    (net (code "43") (name "unconnected-(LED1---Pad2)") (class "Default")
      (node (ref "LED1") (pin "2") (pinfunction "-_2") (pintype "input+no_connect"))
    )
    (net (code "44") (name "unconnected-(SW1-Pad3)") (class "Default")
      (node (ref "SW1") (pin "3") (pinfunction "3_3") (pintype "input+no_connect"))
    )
    (net (code "45") (name "unconnected-(SW1-Pad4)") (class "Default")
      (node (ref "SW1") (pin "4") (pinfunction "4_4") (pintype "input+no_connect"))
    )
    (net (code "46") (name "unconnected-(SW1-Pad5)") (class "Default")
      (node (ref "SW1") (pin "5") (pinfunction "5_5") (pintype "input+no_connect"))
    )
    (net (code "47") (name "unconnected-(SW1-Pad6)") (class "Default")
      (node (ref "SW1") (pin "6") (pinfunction "6_6") (pintype "input+no_connect"))
    )
    (net (code "48") (name "unconnected-(SW1-Pad7)") (class "Default")
      (node (ref "SW1") (pin "7") (pinfunction "7_7") (pintype "input+no_connect"))
    )
    (net (code "49") (name "unconnected-(U5-INT2-Pad9)") (class "Default")
      (node (ref "U5") (pin "9") (pinfunction "INT2_9") (pintype "input+no_connect"))
    )
    (net (code "50") (name "unconnected-(U5-OCS_AUX-Pad10)") (class "Default")
      (node (ref "U5") (pin "10") (pinfunction "OCS_AUX_10") (pintype "input+no_connect"))
    )
    (net (code "51") (name "unconnected-(U5-SDO_AUX-Pad11)") (class "Default")
      (node (ref "U5") (pin "11") (pinfunction "SDO_AUX_11") (pintype "input+no_connect"))
    )
    (net (code "52") (name "unconnected-(U6-INT-PadA1)") (class "Default")
      (node (ref "U6") (pin "A1") (pinfunction "INT_A1") (pintype "unspecified+no_connect"))
    )
    (net (code "53") (name "unconnected-(USB1-SBU1-Pad9)") (class "Default")
      (node (ref "USB1") (pin "9") (pinfunction "SBU1_9") (pintype "input+no_connect"))
    )
    (net (code "54") (name "unconnected-(USB1-SBU2-Pad3)") (class "Default")
      (node (ref "USB1") (pin "3") (pinfunction "SBU2_3") (pintype "input+no_connect"))
    )
  )
)
